# Simple_Boost_AA_to_1V8.net
KiCad netlist of a schematic drawn in EAGLE
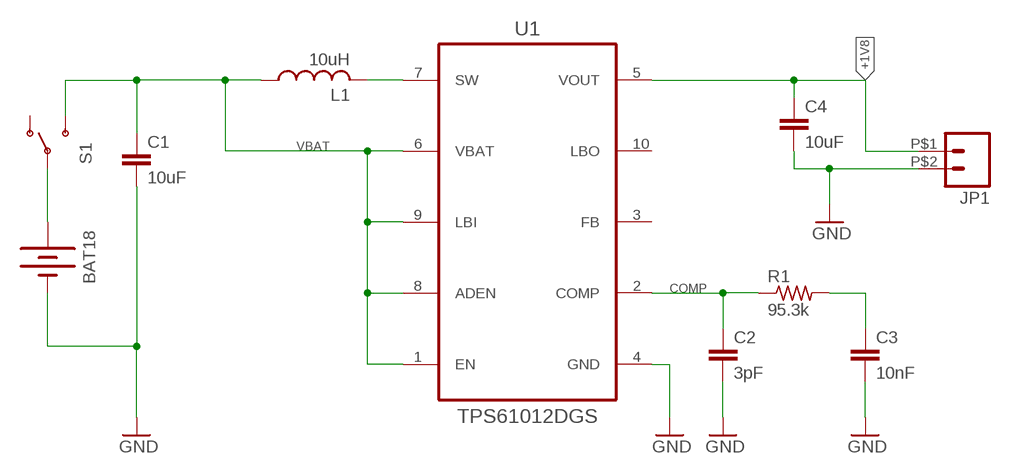
[diagram p0: schematic, sheet 1]

(export (version "E")
  (design (tool "Eeschema 10.0.6"))
  (components
    (comp (ref "BAT18")
      (value "BATTERYAA")
      (footprint "eagle-import:BATTERY-AA")
      (libsource (lib "eagle-import") (part "BATTERYAA"))
    )
    (comp (ref "C1")
      (value "10uF")
      (footprint "eagle-import:C1812")
      (libsource (lib "eagle-import") (part "C-EUC1812"))
    )
    (comp (ref "C2")
      (value "3pF")
      (footprint "eagle-import:C0805")
      (libsource (lib "eagle-import") (part "C-EUC0805"))
    )
    (comp (ref "C3")
      (value "10nF")
      (footprint "eagle-import:C0805")
      (libsource (lib "eagle-import") (part "C-EUC0805"))
    )
    (comp (ref "C4")
      (value "10uF")
      (footprint "eagle-import:C1812")
      (libsource (lib "eagle-import") (part "C-EUC1812"))
    )
    (comp (ref "JP1")
      (value "M02TE-282834-2")
      (footprint "eagle-import:1X02_282834-2")
      (libsource (lib "eagle-import") (part "M02TE-282834-2"))
    )
    (comp (ref "L1")
      (value "10uH")
      (footprint "eagle-import:CDRH6D38")
      (libsource (lib "eagle-import") (part "SUMIDA_POWER_INDUCTOR6"))
    )
    (comp (ref "R1")
      (value "95.3k")
      (footprint "eagle-import:R0805")
      (libsource (lib "eagle-import") (part "R-US_R0805"))
    )
    (comp (ref "S1")
      (value "SWITCH-SPDTPTH")
      (footprint "eagle-import:SWITCH-SPDT")
      (libsource (lib "eagle-import") (part "SWITCH-SPDTPTH"))
    )
    (comp (ref "U1")
      (value "TPS61012DGS")
      (footprint "eagle-import:SOP50P490X110-10N")
      (fields (field (name "VOLTAGE") "1.8"))
      (libsource (lib "eagle-import") (part "TPS6101DGS2"))
    )
  )
  (nets
    (net (code "1") (name "+1V8") (class "Default")
      (node (ref "C4") (pin "1") (pinfunction "1_1") (pintype "passive"))
      (node (ref "JP1") (pin "P$1") (pinfunction "1_P$1") (pintype "passive"))
      (node (ref "U1") (pin "5") (pinfunction "VOUT_5") (pintype "output"))
    )
    (net (code "2") (name "/COMP") (class "Default")
      (node (ref "C2") (pin "1") (pinfunction "1_1") (pintype "passive"))
      (node (ref "R1") (pin "1") (pinfunction "1_1") (pintype "passive"))
      (node (ref "U1") (pin "2") (pinfunction "COMP_2") (pintype "input"))
    )
    (net (code "3") (name "/VBAT") (class "Default")
      (node (ref "C1") (pin "1") (pinfunction "1_1") (pintype "passive"))
      (node (ref "L1") (pin "P$1") (pinfunction "1_P$1") (pintype "passive"))
      (node (ref "S1") (pin "3") (pinfunction "S_3") (pintype "passive"))
      (node (ref "U1") (pin "1") (pinfunction "EN_1") (pintype "input"))
      (node (ref "U1") (pin "6") (pinfunction "VBAT_6") (pintype "power_in"))
      (node (ref "U1") (pin "8") (pinfunction "ADEN_8") (pintype "input"))
      (node (ref "U1") (pin "9") (pinfunction "LBI_9") (pintype "input"))
    )
    (net (code "4") (name "GND") (class "Default")
      (node (ref "BAT18") (pin "GND@1") (pinfunction "-_GND@1") (pintype "power_in"))
      (node (ref "BAT18") (pin "GND@2") (pinfunction "-_GND@2") (pintype "power_in"))
      (node (ref "C1") (pin "2") (pinfunction "2_2") (pintype "passive"))
      (node (ref "C2") (pin "2") (pinfunction "2_2") (pintype "passive"))
      (node (ref "C3") (pin "2") (pinfunction "2_2") (pintype "passive"))
      (node (ref "C4") (pin "2") (pinfunction "2_2") (pintype "passive"))
      (node (ref "JP1") (pin "P$2") (pinfunction "2_P$2") (pintype "passive"))
      (node (ref "U1") (pin "4") (pinfunction "GND_4") (pintype "passive"))
    )
    (net (code "5") (name "Net-(C3-Pad1)") (class "Default")
      (node (ref "C3") (pin "1") (pinfunction "1_1") (pintype "passive"))
      (node (ref "R1") (pin "2") (pinfunction "2_2") (pintype "passive"))
    )
    (net (code "6") (name "Net-(L1-2)") (class "Default")
      (node (ref "L1") (pin "P$2") (pinfunction "2_P$2") (pintype "passive"))
      (node (ref "U1") (pin "7") (pinfunction "SW_7") (pintype "input"))
    )
    (net (code "7") (name "Net-(S1-P)") (class "Default")
      (node (ref "BAT18") (pin "PWR@1") (pinfunction "+_PWR@1") (pintype "power_in"))
      (node (ref "BAT18") (pin "PWR@2") (pinfunction "+_PWR@2") (pintype "power_in"))
      (node (ref "S1") (pin "2") (pinfunction "P_2") (pintype "passive"))
    )
    (net (code "8") (name "unconnected-(S1-O-Pad1)") (class "Default")
      (node (ref "S1") (pin "1") (pinfunction "O_1") (pintype "passive"))
    )
    (net (code "9") (name "unconnected-(U1-FB-Pad3)") (class "Default")
      (node (ref "U1") (pin "3") (pinfunction "FB_3") (pintype "input"))
    )
    (net (code "10") (name "unconnected-(U1-LBO-Pad10)") (class "Default")
      (node (ref "U1") (pin "10") (pinfunction "LBO_10") (pintype "output"))
    )
  )
)
